# Sheet1.net
KiCad netlist of a schematic drawn in Altium Designer
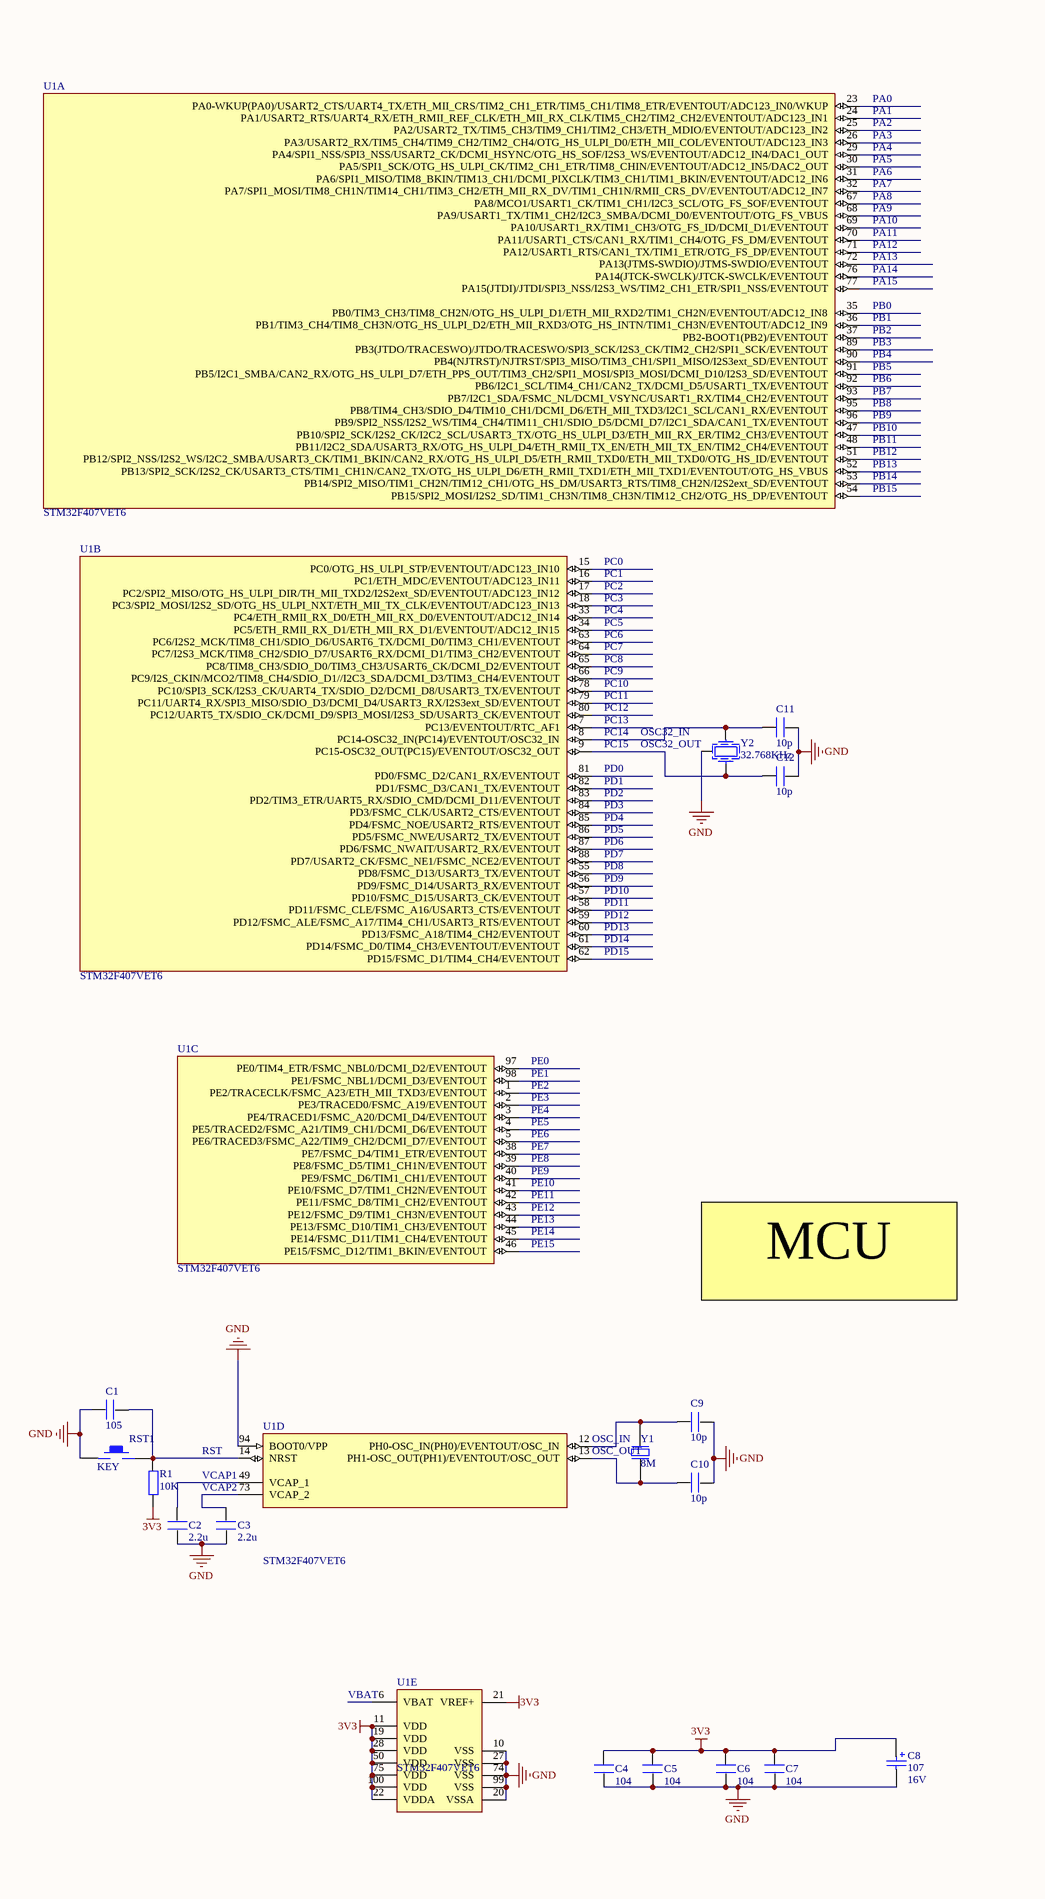
[diagram p0: Sheet1.SchDoc, left]
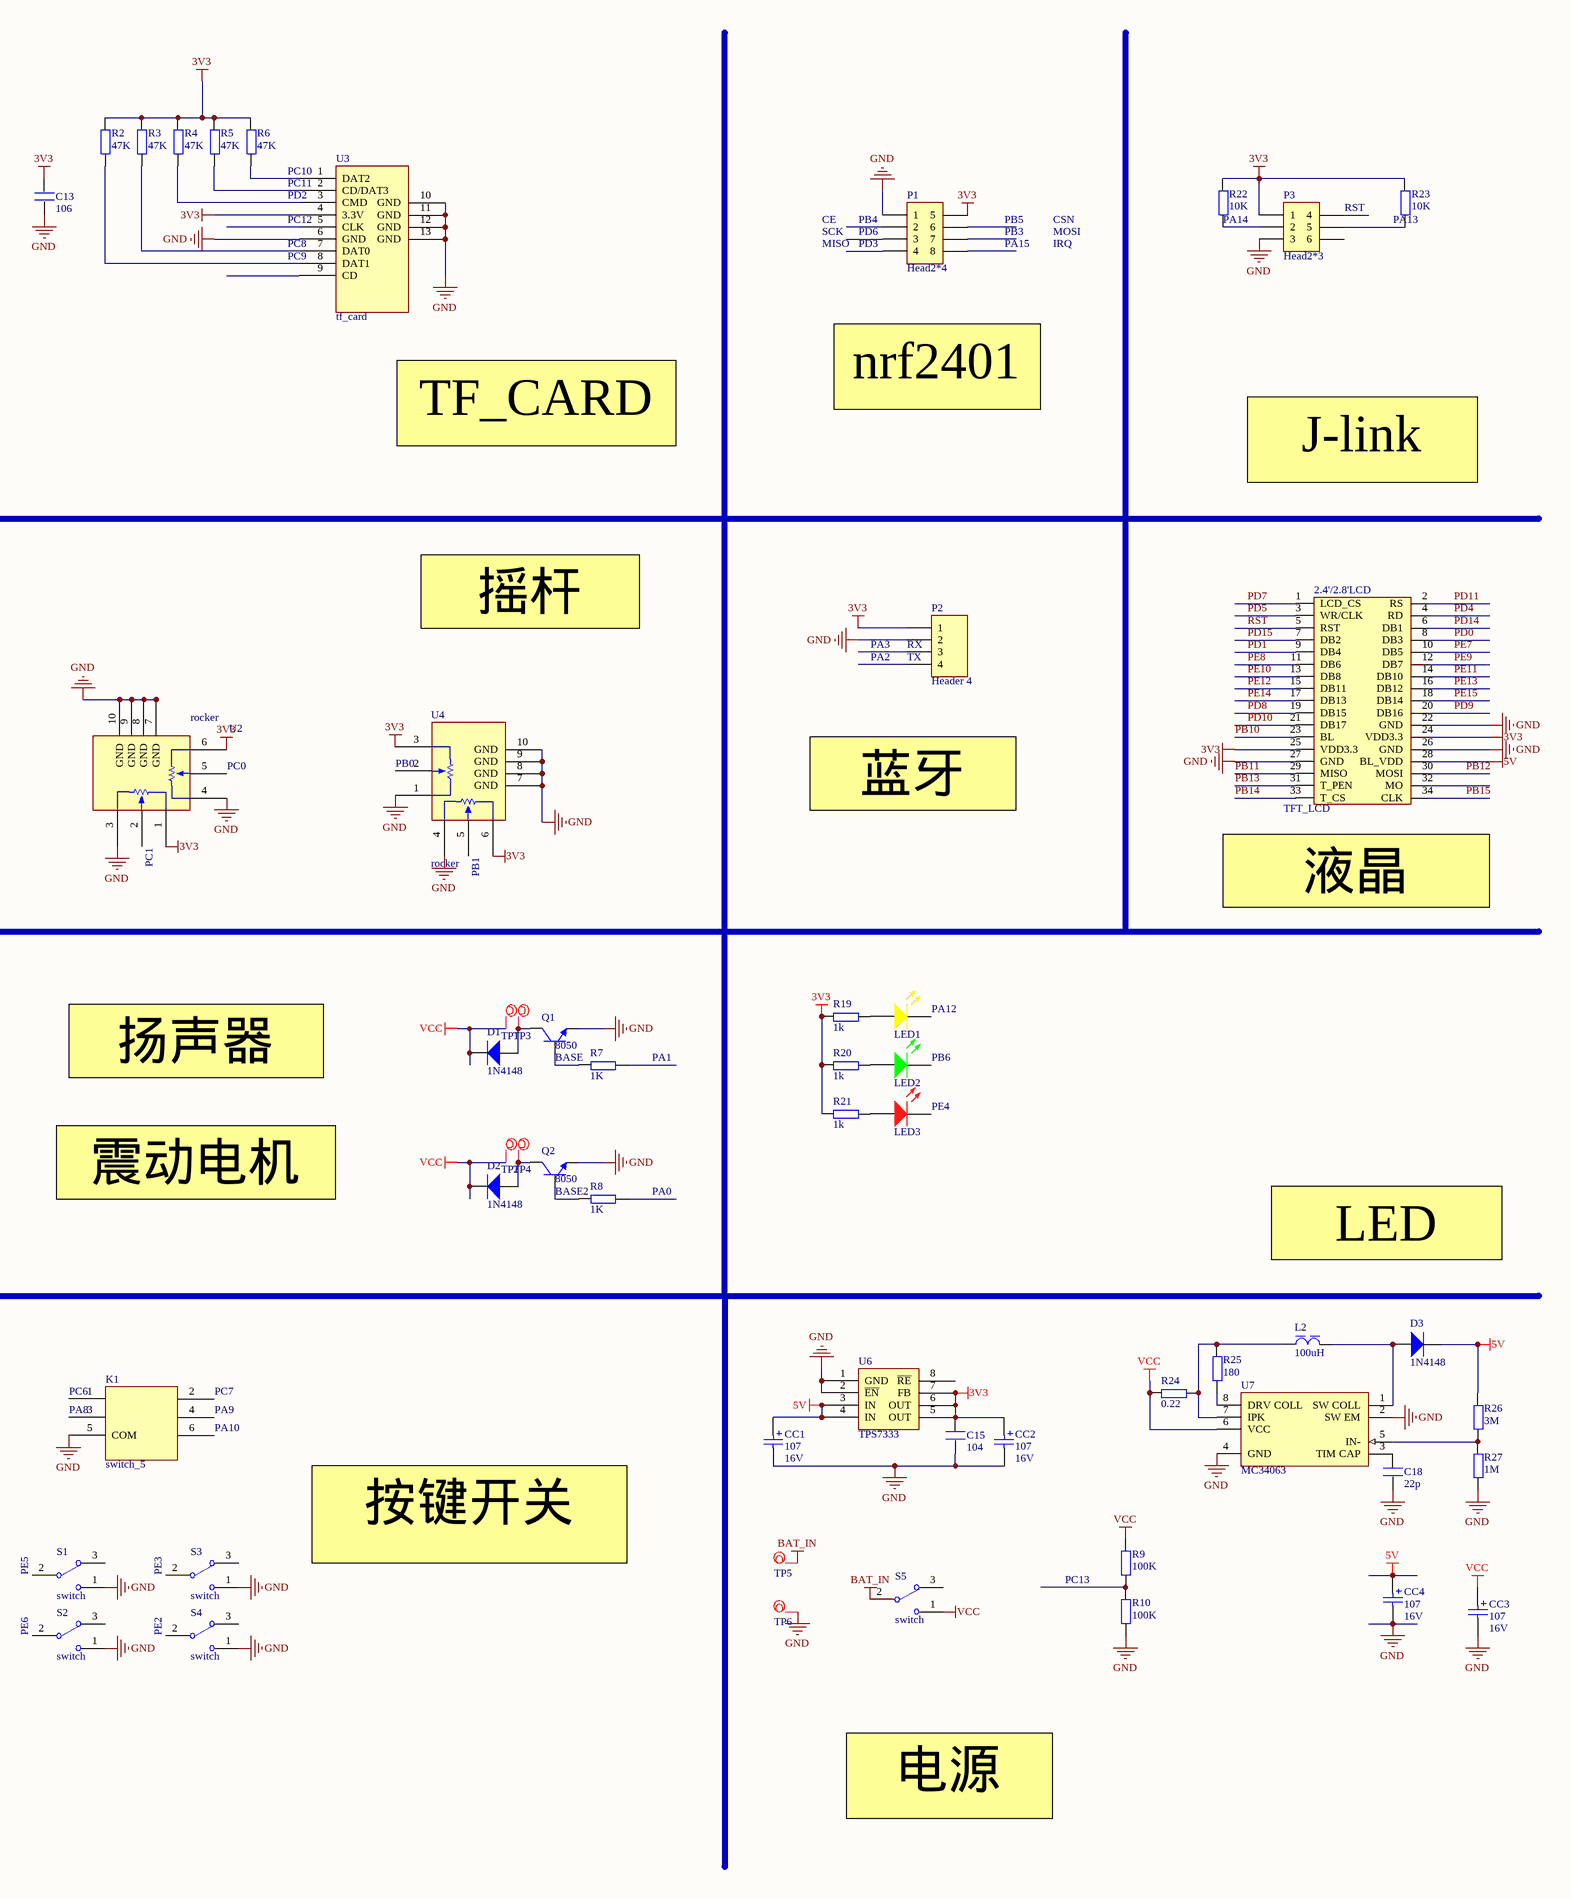
[diagram p1: Sheet1.SchDoc, right]

(export (version "E")
  (design (tool "Eeschema 10.0.6"))
  (components
    (comp (ref "2.4'/2.8'LCD")
      (value "TFT_LCD")
      (footprint "HDR2X17")
      (libsource (lib "战舰STM32开发板底板封装库") (part "TFT_LCD"))
    )
    (comp (ref "C1") (value "105") (footprint "0805C") (libsource (lib "WARSHIP") (part "C")))
    (comp (ref "C2") (value "2.2u") (footprint "0805C") (libsource (lib "WARSHIP") (part "C")))
    (comp (ref "C3") (value "2.2u") (footprint "0805C") (libsource (lib "WARSHIP") (part "C")))
    (comp (ref "C4") (value "104") (footprint "0805C") (libsource (lib "WARSHIP") (part "C")))
    (comp (ref "C5") (value "104") (footprint "0805C") (libsource (lib "WARSHIP") (part "C")))
    (comp (ref "C6") (value "104") (footprint "0805C") (libsource (lib "WARSHIP") (part "C")))
    (comp (ref "C7") (value "104") (footprint "0805C") (libsource (lib "WARSHIP") (part "C")))
    (comp (ref "C8")
      (value "107")
      (footprint "CAPT6032")
      (description "Molded (Tantalum) Capacitor, 2-Leads,")
      (fields (field (name "VOLTAGE") "16V") (field (name "PUBLISHER") "Altium Limited"))
      (libsource (lib "!)Miscellaneous Integrated Library") (part "Cap Tan"))
    )
    (comp (ref "C9") (value "10p") (footprint "0805C") (libsource (lib "WARSHIP") (part "C")))
    (comp (ref "C10") (value "10p") (footprint "0805C") (libsource (lib "WARSHIP") (part "C")))
    (comp (ref "C11") (value "10p") (footprint "0805C") (libsource (lib "WARSHIP") (part "C")))
    (comp (ref "C12") (value "10p") (footprint "0805C") (libsource (lib "WARSHIP") (part "C")))
    (comp (ref "C13") (value "106") (footprint "0805C") (libsource (lib "WARSHIP") (part "C")))
    (comp (ref "C15") (value "104") (footprint "0805C") (libsource (lib "WARSHIP") (part "C")))
    (comp (ref "C18") (value "22p") (footprint "0805C") (libsource (lib "WARSHIP") (part "C")))
    (comp (ref "CC1")
      (value "107")
      (footprint "CAPT6032")
      (description "Molded (Tantalum) Capacitor, 2-Leads,")
      (fields (field (name "VOLTAGE") "16V") (field (name "PUBLISHER") "Altium Limited"))
      (libsource (lib "!)Miscellaneous Integrated Library") (part "Cap Tan"))
    )
    (comp (ref "CC2")
      (value "107")
      (footprint "CAPT6032")
      (description "Molded (Tantalum) Capacitor, 2-Leads,")
      (fields (field (name "VOLTAGE") "16V") (field (name "PUBLISHER") "Altium Limited"))
      (libsource (lib "!)Miscellaneous Integrated Library") (part "Cap Tan"))
    )
    (comp (ref "CC3")
      (value "107")
      (footprint "CAPT6032")
      (description "Molded (Tantalum) Capacitor, 2-Leads,")
      (fields (field (name "VOLTAGE") "16V") (field (name "PUBLISHER") "Altium Limited"))
      (libsource (lib "!)Miscellaneous Integrated Library") (part "Cap Tan"))
    )
    (comp (ref "CC4")
      (value "107")
      (footprint "CAPT6032")
      (description "Molded (Tantalum) Capacitor, 2-Leads,")
      (fields (field (name "VOLTAGE") "16V") (field (name "PUBLISHER") "Altium Limited"))
      (libsource (lib "!)Miscellaneous Integrated Library") (part "Cap Tan"))
    )
    (comp (ref "D1")
      (value "1N4148")
      (footprint "SOD-80[LL-34]")
      (description "SMT Glass Diode, PSpice Model")
      (fields (field (name "PARTNUMBER") "1N4148") (field (name "PUBLISHER") "Altium Limited"))
      (libsource (lib "!)Miscellaneous Integrated Library") (part "Diode 1N4148"))
    )
    (comp (ref "D2")
      (value "1N4148")
      (footprint "SOD-80[LL-34]")
      (description "SMT Glass Diode, PSpice Model")
      (fields (field (name "PARTNUMBER") "1N4148") (field (name "PUBLISHER") "Altium Limited"))
      (libsource (lib "!)Miscellaneous Integrated Library") (part "Diode 1N4148"))
    )
    (comp (ref "D3")
      (value "1N4148")
      (footprint "SOD-80[LL-34]")
      (description "SMT Glass Diode, PSpice Model")
      (fields (field (name "PARTNUMBER") "1N4148") (field (name "PUBLISHER") "Altium Limited"))
      (libsource (lib "!)Miscellaneous Integrated Library") (part "Diode 1N4148"))
    )
    (comp (ref "K1") (value "switch_5") (footprint "switch_5") (libsource (lib "电磁组") (part "switch_5")))
    (comp (ref "L2")
      (value "100uH")
      (footprint "CD75")
      (description "Power Inductor, Ferrite-Core")
      (fields (field (name "PUBLISHER") "Altium Limited"))
      (libsource (lib "!)Miscellaneous Integrated Library") (part "Ind Power"))
    )
    (comp (ref "LED1")
      (value "LED 3Y")
      (footprint "LED-R3-H5-SINGLE-Y")
      (description "Yellow, 3mm, Typical INFRARED GaAs LED")
      (fields (field (name "PUBLISHER") "Altium Limited"))
      (libsource (lib "!)Miscellaneous Integrated Library") (part "LED 3Y"))
    )
    (comp (ref "LED2")
      (value "LED 3G")
      (footprint "LED-R3-H5-SINGLE-G")
      (description "Green, 3mm, Typical INFRARED GaAs LED")
      (fields (field (name "PUBLISHER") "Altium Limited"))
      (libsource (lib "!)Miscellaneous Integrated Library") (part "LED 3G"))
    )
    (comp (ref "LED3")
      (value "LED 3R")
      (footprint "LED-R3-H5-SINGLE-R")
      (description "Red, 3mm, Typical INFRARED GaAs LED")
      (fields (field (name "PUBLISHER") "Altium Limited"))
      (libsource (lib "!)Miscellaneous Integrated Library") (part "LED 3R"))
    )
    (comp (ref "P1")
      (value "Head2*4")
      (footprint "Header2x4_chip")
      (libsource (lib "电磁组") (part "Header2x4"))
    )
    (comp (ref "P2")
      (value "Header 4")
      (footprint "HX2.54V-4")
      (description "Header, 4-Pin")
      (fields (field (name "PUBLISHER") "Altium Limited"))
      (libsource (lib "!)Miscellaneous Integrated Library") (part "Header 4"))
    )
    (comp (ref "P3")
      (value "Head2*3")
      (footprint "Header2x3_chip")
      (libsource (lib "电磁组") (part "Header2x3"))
    )
    (comp (ref "Q1")
      (value "8050")
      (footprint "SOT23")
      (description "NPN Bipolar Transistor")
      (fields (field (name "PARTNUMBER") "8050") (field (name "PUBLISHER") "Altium Limited"))
      (libsource (lib "!)Miscellaneous Integrated Library") (part "NPN BC817-40"))
    )
    (comp (ref "Q2")
      (value "8050")
      (footprint "SOT23")
      (description "NPN Bipolar Transistor")
      (fields (field (name "PARTNUMBER") "8050") (field (name "PUBLISHER") "Altium Limited"))
      (libsource (lib "!)Miscellaneous Integrated Library") (part "NPN BC817-40"))
    )
    (comp (ref "R1") (value "10K") (footprint "0805R") (libsource (lib "WARSHIP") (part "R")))
    (comp (ref "R2") (value "47K") (footprint "0805R") (libsource (lib "WARSHIP") (part "R")))
    (comp (ref "R3") (value "47K") (footprint "0805R") (libsource (lib "WARSHIP") (part "R")))
    (comp (ref "R4") (value "47K") (footprint "0805R") (libsource (lib "WARSHIP") (part "R")))
    (comp (ref "R5") (value "47K") (footprint "0805R") (libsource (lib "WARSHIP") (part "R")))
    (comp (ref "R6") (value "47K") (footprint "0805R") (libsource (lib "WARSHIP") (part "R")))
    (comp (ref "R7") (value "1K") (footprint "0805R") (libsource (lib "WARSHIP") (part "R")))
    (comp (ref "R8") (value "1K") (footprint "0805R") (libsource (lib "WARSHIP") (part "R")))
    (comp (ref "R9") (value "100K") (footprint "0805R") (libsource (lib "WARSHIP") (part "R")))
    (comp (ref "R10") (value "100K") (footprint "0805R") (libsource (lib "WARSHIP") (part "R")))
    (comp (ref "R19") (value "1k") (footprint "0805R") (libsource (lib "WARSHIP") (part "R")))
    (comp (ref "R20") (value "1k") (footprint "0805R") (libsource (lib "WARSHIP") (part "R")))
    (comp (ref "R21") (value "1k") (footprint "0805R") (libsource (lib "WARSHIP") (part "R")))
    (comp (ref "R22") (value "10K") (footprint "0805R") (libsource (lib "WARSHIP") (part "R")))
    (comp (ref "R23") (value "10K") (footprint "0805R") (libsource (lib "WARSHIP") (part "R")))
    (comp (ref "R24") (value "0.22") (footprint "0805R") (libsource (lib "WARSHIP") (part "R")))
    (comp (ref "R25") (value "180") (footprint "0805R") (libsource (lib "WARSHIP") (part "R")))
    (comp (ref "R26") (value "3M") (footprint "0805R") (libsource (lib "WARSHIP") (part "R")))
    (comp (ref "R27") (value "1M") (footprint "0805R") (libsource (lib "WARSHIP") (part "R")))
    (comp (ref "RST1") (value "KEY") (footprint "KEY") (libsource (lib "电磁组") (part "KEY")))
    (comp (ref "S1") (value "switch") (footprint "switch4") (libsource (lib "电磁组") (part "MIANkey")))
    (comp (ref "S2") (value "switch") (footprint "switch4") (libsource (lib "电磁组") (part "MIANkey")))
    (comp (ref "S3") (value "switch") (footprint "switch4") (libsource (lib "电磁组") (part "MIANkey")))
    (comp (ref "S4") (value "switch") (footprint "switch4") (libsource (lib "电磁组") (part "MIANkey")))
    (comp (ref "S5") (value "switch") (footprint "swtich3") (libsource (lib "电磁组") (part "MIANkey")))
    (comp (ref "TP1")
      (value "Test Point")
      (footprint "TESTPOINT_PAD_3")
      (description "Test Point for Manufature")
      (libsource (lib "!)Miscellaneous Integrated Library") (part "Test Point"))
    )
    (comp (ref "TP2")
      (value "Test Point")
      (footprint "TESTPOINT_PAD_3")
      (description "Test Point for Manufature")
      (libsource (lib "!)Miscellaneous Integrated Library") (part "Test Point"))
    )
    (comp (ref "TP3")
      (value "Test Point")
      (footprint "TESTPOINT_PAD_3")
      (description "Test Point for Manufature")
      (libsource (lib "!)Miscellaneous Integrated Library") (part "Test Point"))
    )
    (comp (ref "TP4")
      (value "Test Point")
      (footprint "TESTPOINT_PAD_3")
      (description "Test Point for Manufature")
      (libsource (lib "!)Miscellaneous Integrated Library") (part "Test Point"))
    )
    (comp (ref "TP5")
      (value "Test Point")
      (footprint "TESTPOINT_PAD_3")
      (description "Test Point for Manufature")
      (libsource (lib "!)Miscellaneous Integrated Library") (part "Test Point"))
    )
    (comp (ref "TP6")
      (value "Test Point")
      (footprint "TESTPOINT_PAD_3")
      (description "Test Point for Manufature")
      (libsource (lib "!)Miscellaneous Integrated Library") (part "Test Point"))
    )
    (comp (ref "U1")
      (value "STM32F407VET6")
      (footprint "LQFP100_M")
      (libsource (lib "STMicroelectronics STM32 F4") (part "STM32F407VET6"))
    )
    (comp (ref "U2") (value "rocker") (footprint "Rocker") (libsource (lib "电磁组") (part "rocker")))
    (comp (ref "U3") (value "tf_card") (footprint "TF-2") (libsource (lib "电磁组") (part "TF- SDIO")))
    (comp (ref "U4") (value "rocker") (footprint "Rocker") (libsource (lib "") (part "rocker_1")))
    (comp (ref "U6") (value "TPS7333") (footprint "TPS7333") (libsource (lib "Schlib1") (part "TPS7333")))
    (comp (ref "U7")
      (value "MC34063")
      (footprint "SOIC8")
      (description "DC-to-DC Converter Control Circuit")
      (fields (field (name "PARTNUMBER") "MC34063"))
      (libsource (lib "!)Miscellaneous Integrated Library") (part "MC34063"))
    )
    (comp (ref "Y1")
      (value "8M")
      (footprint "XTAL-SMD")
      (description "Crystal Oscillator")
      (fields (field (name "PUBLISHER") "Altium Limited"))
      (libsource (lib "!)Miscellaneous Integrated Library") (part "XTAL"))
    )
    (comp (ref "Y2")
      (value "32.768KHz")
      (footprint "XTAL")
      (description "3-pin Crystal Oscillator, Case Shelter")
      (libsource (lib "!)Miscellaneous Integrated Library") (part "XTAL 3P"))
    )
  )
  (nets
    (net (code "1") (name "/BASE") (class "Default")
      (node (ref "Q1") (pin "1") (pinfunction "B_1") (pintype "passive"))
      (node (ref "R7") (pin "1") (pintype "passive"))
    )
    (net (code "2") (name "/BASE2") (class "Default")
      (node (ref "Q2") (pin "1") (pinfunction "B_1") (pintype "passive"))
      (node (ref "R8") (pin "1") (pintype "passive"))
    )
    (net (code "8") (name "/OSC32_IN") (class "Default")
      (node (ref "C11") (pin "1") (pintype "passive"))
      (node (ref "U1") (pin "8") (pinfunction "PC14-OSC32_IN(PC14)/EVENTOUT/OSC32_IN_8") (pintype "bidirectional"))
      (node (ref "Y2") (pin "1") (pintype "passive"))
    )
    (net (code "9") (name "/OSC32_OUT") (class "Default")
      (node (ref "C12") (pin "1") (pintype "passive"))
      (node (ref "U1") (pin "9") (pinfunction "PC15-OSC32_OUT(PC15)/EVENTOUT/OSC32_OUT_9") (pintype "bidirectional"))
      (node (ref "Y2") (pin "2") (pintype "passive"))
    )
    (net (code "10") (name "/OSC_IN") (class "Default")
      (node (ref "C9") (pin "1") (pintype "passive"))
      (node (ref "U1") (pin "12") (pinfunction "PH0-OSC_IN(PH0)/EVENTOUT/OSC_IN_12") (pintype "bidirectional"))
      (node (ref "Y1") (pin "2") (pinfunction "OSC2_2") (pintype "passive"))
    )
    (net (code "11") (name "/OSC_OUT") (class "Default")
      (node (ref "C10") (pin "1") (pintype "passive"))
      (node (ref "U1") (pin "13") (pinfunction "PH1-OSC_OUT(PH1)/EVENTOUT/OSC_OUT_13") (pintype "bidirectional"))
      (node (ref "Y1") (pin "1") (pinfunction "OSC1_1") (pintype "passive"))
    )
    (net (code "12") (name "/PA0") (class "Default")
      (node (ref "R8") (pin "2") (pintype "passive"))
      (node (ref "U1") (pin "23") (pinfunction "PA0-WKUP(PA0)/USART2_CTS/UART4_TX/ETH_MII_CRS/TIM2_CH1_ETR/TIM5_CH1/TIM8_ETR/EVENTOUT/ADC123_IN0/WKUP_23") (pintype "bidirectional"))
    )
    (net (code "13") (name "/PA1") (class "Default")
      (node (ref "R7") (pin "2") (pintype "passive"))
      (node (ref "U1") (pin "24") (pinfunction "PA1/USART2_RTS/UART4_RX/ETH_RMII_REF_CLK/ETH_MII_RX_CLK/TIM5_CH2/TIM2_CH2/EVENTOUT/ADC123_IN1_24") (pintype "bidirectional"))
    )
    (net (code "14") (name "/PA2") (class "Default")
      (node (ref "P2") (pin "4") (pinfunction "4_4") (pintype "passive"))
      (node (ref "U1") (pin "25") (pinfunction "PA2/USART2_TX/TIM5_CH3/TIM9_CH1/TIM2_CH3/ETH_MDIO/EVENTOUT/ADC123_IN2_25") (pintype "bidirectional"))
    )
    (net (code "15") (name "/PA3") (class "Default")
      (node (ref "P2") (pin "3") (pinfunction "3_3") (pintype "passive"))
      (node (ref "U1") (pin "26") (pinfunction "PA3/USART2_RX/TIM5_CH4/TIM9_CH2/TIM2_CH4/OTG_HS_ULPI_D0/ETH_MII_COL/EVENTOUT/ADC123_IN3_26") (pintype "bidirectional"))
    )
    (net (code "16") (name "/PA4") (class "Default")
      (node (ref "U1") (pin "29") (pinfunction "PA4/SPI1_NSS/SPI3_NSS/USART2_CK/DCMI_HSYNC/OTG_HS_SOF/I2S3_WS/EVENTOUT/ADC12_IN4/DAC1_OUT_29") (pintype "bidirectional"))
    )
    (net (code "17") (name "/PA5") (class "Default")
      (node (ref "U1") (pin "30") (pinfunction "PA5/SPI1_SCK/OTG_HS_ULPI_CK/TIM2_CH1_ETR/TIM8_CHIN/EVENTOUT/ADC12_IN5/DAC2_OUT_30") (pintype "bidirectional"))
    )
    (net (code "18") (name "/PA6") (class "Default")
      (node (ref "U1") (pin "31") (pinfunction "PA6/SPI1_MISO/TIM8_BKIN/TIM13_CH1/DCMI_PIXCLK/TIM3_CH1/TIM1_BKIN/EVENTOUT/ADC12_IN6_31") (pintype "bidirectional"))
    )
    (net (code "19") (name "/PA7") (class "Default")
      (node (ref "U1") (pin "32") (pinfunction "PA7/SPI1_MOSI/TIM8_CH1N/TIM14_CH1/TIM3_CH2/ETH_MII_RX_DV/TIM1_CH1N/RMII_CRS_DV/EVENTOUT/ADC12_IN7_32") (pintype "bidirectional"))
    )
    (net (code "20") (name "/PA8") (class "Default")
      (node (ref "K1") (pin "3") (pintype "passive"))
      (node (ref "U1") (pin "67") (pinfunction "PA8/MCO1/USART1_CK/TIM1_CH1/I2C3_SCL/OTG_FS_SOF/EVENTOUT_67") (pintype "bidirectional"))
    )
    (net (code "21") (name "/PA9") (class "Default")
      (node (ref "K1") (pin "4") (pintype "passive"))
      (node (ref "U1") (pin "68") (pinfunction "PA9/USART1_TX/TIM1_CH2/I2C3_SMBA/DCMI_D0/EVENTOUT/OTG_FS_VBUS_68") (pintype "bidirectional"))
    )
    (net (code "22") (name "/PA10") (class "Default")
      (node (ref "K1") (pin "6") (pintype "passive"))
      (node (ref "U1") (pin "69") (pinfunction "PA10/USART1_RX/TIM1_CH3/OTG_FS_ID/DCMI_D1/EVENTOUT_69") (pintype "bidirectional"))
    )
    (net (code "23") (name "/PA11") (class "Default")
      (node (ref "U1") (pin "70") (pinfunction "PA11/USART1_CTS/CAN1_RX/TIM1_CH4/OTG_FS_DM/EVENTOUT_70") (pintype "bidirectional"))
    )
    (net (code "24") (name "/PA12") (class "Default")
      (node (ref "LED1") (pin "2") (pinfunction "K_2") (pintype "passive"))
      (node (ref "U1") (pin "71") (pinfunction "PA12/USART1_RTS/CAN1_TX/TIM1_ETR/OTG_FS_DP/EVENTOUT_71") (pintype "bidirectional"))
    )
    (net (code "25") (name "/PA13") (class "Default")
      (node (ref "P3") (pin "5") (pinfunction "5_5") (pintype "passive"))
      (node (ref "R23") (pin "1") (pintype "passive"))
      (node (ref "U1") (pin "72") (pinfunction "PA13(JTMS-SWDIO)/JTMS-SWDIO/EVENTOUT_72") (pintype "bidirectional"))
    )
    (net (code "26") (name "/PA14") (class "Default")
      (node (ref "P3") (pin "2") (pinfunction "2_2") (pintype "passive"))
      (node (ref "R22") (pin "1") (pintype "passive"))
      (node (ref "U1") (pin "76") (pinfunction "PA14(JTCK-SWCLK)/JTCK-SWCLK/EVENTOUT_76") (pintype "bidirectional"))
    )
    (net (code "27") (name "/PA15") (class "Default")
      (node (ref "P1") (pin "8") (pinfunction "8_8") (pintype "passive"))
      (node (ref "U1") (pin "77") (pinfunction "PA15(JTDI)/JTDI/SPI3_NSS/I2S3_WS/TIM2_CH1_ETR/SPI1_NSS/EVENTOUT_77") (pintype "bidirectional"))
    )
    (net (code "28") (name "/PB0") (class "Default")
      (node (ref "U1") (pin "35") (pinfunction "PB0/TIM3_CH3/TIM8_CH2N/OTG_HS_ULPI_D1/ETH_MII_RXD2/TIM1_CH2N/EVENTOUT/ADC12_IN8_35") (pintype "bidirectional"))
      (node (ref "U4") (pin "2") (pintype "passive"))
    )
    (net (code "29") (name "/PB1") (class "Default")
      (node (ref "U1") (pin "36") (pinfunction "PB1/TIM3_CH4/TIM8_CH3N/OTG_HS_ULPI_D2/ETH_MII_RXD3/OTG_HS_INTN/TIM1_CH3N/EVENTOUT/ADC12_IN9_36") (pintype "bidirectional"))
      (node (ref "U4") (pin "5") (pintype "passive"))
    )
    (net (code "30") (name "/PB2") (class "Default")
      (node (ref "U1") (pin "37") (pinfunction "PB2-BOOT1(PB2)/EVENTOUT_37") (pintype "bidirectional"))
    )
    (net (code "31") (name "/PB3") (class "Default")
      (node (ref "P1") (pin "7") (pinfunction "7_7") (pintype "passive"))
      (node (ref "U1") (pin "89") (pinfunction "PB3(JTDO/TRACESWO)/JTDO/TRACESWO/SPI3_SCK/I2S3_CK/TIM2_CH2/SPI1_SCK/EVENTOUT_89") (pintype "bidirectional"))
    )
    (net (code "32") (name "/PB4") (class "Default")
      (node (ref "P1") (pin "2") (pinfunction "2_2") (pintype "passive"))
      (node (ref "U1") (pin "90") (pinfunction "PB4(NJTRST)/NJTRST/SPI3_MISO/TIM3_CH1/SPI1_MISO/I2S3ext_SD/EVENTOUT_90") (pintype "bidirectional"))
    )
    (net (code "33") (name "/PB5") (class "Default")
      (node (ref "P1") (pin "6") (pinfunction "6_6") (pintype "passive"))
      (node (ref "U1") (pin "91") (pinfunction "PB5/I2C1_SMBA/CAN2_RX/OTG_HS_ULPI_D7/ETH_PPS_OUT/TIM3_CH2/SPI1_MOSI/SPI3_MOSI/DCMI_D10/I2S3_SD/EVENTOUT_91") (pintype "bidirectional"))
    )
    (net (code "34") (name "/PB6") (class "Default")
      (node (ref "LED2") (pin "2") (pinfunction "K_2") (pintype "passive"))
      (node (ref "U1") (pin "92") (pinfunction "PB6/I2C1_SCL/TIM4_CH1/CAN2_TX/DCMI_D5/USART1_TX/EVENTOUT_92") (pintype "bidirectional"))
    )
    (net (code "35") (name "/PB7") (class "Default")
      (node (ref "U1") (pin "93") (pinfunction "PB7/I2C1_SDA/FSMC_NL/DCMI_VSYNC/USART1_RX/TIM4_CH2/EVENTOUT_93") (pintype "bidirectional"))
    )
    (net (code "36") (name "/PB8") (class "Default")
      (node (ref "U1") (pin "95") (pinfunction "PB8/TIM4_CH3/SDIO_D4/TIM10_CH1/DCMI_D6/ETH_MII_TXD3/I2C1_SCL/CAN1_RX/EVENTOUT_95") (pintype "bidirectional"))
    )
    (net (code "37") (name "/PB9") (class "Default")
      (node (ref "U1") (pin "96") (pinfunction "PB9/SPI2_NSS/I2S2_WS/TIM4_CH4/TIM11_CH1/SDIO_D5/DCMI_D7/I2C1_SDA/CAN1_TX/EVENTOUT_96") (pintype "bidirectional"))
    )
    (net (code "38") (name "/PB10") (class "Default")
      (node (ref "2.4'/2.8'LCD") (pin "23") (pinfunction "BL_23") (pintype "passive"))
      (node (ref "U1") (pin "47") (pinfunction "PB10/SPI2_SCK/I2S2_CK/I2C2_SCL/USART3_TX/OTG_HS_ULPI_D3/ETH_MII_RX_ER/TIM2_CH3/EVENTOUT_47") (pintype "bidirectional"))
    )
    (net (code "39") (name "/PB11") (class "Default")
      (node (ref "2.4'/2.8'LCD") (pin "29") (pinfunction "MISO_29") (pintype "passive"))
      (node (ref "U1") (pin "48") (pinfunction "PB11/I2C2_SDA/USART3_RX/OTG_HS_ULPI_D4/ETH_RMII_TX_EN/ETH_MII_TX_EN/TIM2_CH4/EVENTOUT_48") (pintype "bidirectional"))
    )
    (net (code "40") (name "/PB12") (class "Default")
      (node (ref "2.4'/2.8'LCD") (pin "30") (pinfunction "MOSI_30") (pintype "passive"))
      (node (ref "U1") (pin "51") (pinfunction "PB12/SPI2_NSS/I2S2_WS/I2C2_SMBA/USART3_CK/TIM1_BKIN/CAN2_RX/OTG_HS_ULPI_D5/ETH_RMII_TXD0/ETH_MII_TXD0/OTG_HS_ID/EVENTOUT_51") (pintype "bidirectional"))
    )
    (net (code "41") (name "/PB13") (class "Default")
      (node (ref "2.4'/2.8'LCD") (pin "31") (pinfunction "T_PEN_31") (pintype "passive"))
      (node (ref "U1") (pin "52") (pinfunction "PB13/SPI2_SCK/I2S2_CK/USART3_CTS/TIM1_CH1N/CAN2_TX/OTG_HS_ULPI_D6/ETH_RMII_TXD1/ETH_MII_TXD1/EVENTOUT/OTG_HS_VBUS_52") (pintype "bidirectional"))
    )
    (net (code "42") (name "/PB14") (class "Default")
      (node (ref "2.4'/2.8'LCD") (pin "33") (pinfunction "T_CS_33") (pintype "passive"))
      (node (ref "U1") (pin "53") (pinfunction "PB14/SPI2_MISO/TIM1_CH2N/TIM12_CH1/OTG_HS_DM/USART3_RTS/TIM8_CH2N/I2S2ext_SD/EVENTOUT_53") (pintype "bidirectional"))
    )
    (net (code "43") (name "/PB15") (class "Default")
      (node (ref "2.4'/2.8'LCD") (pin "34") (pinfunction "CLK_34") (pintype "passive"))
      (node (ref "U1") (pin "54") (pinfunction "PB15/SPI2_MOSI/I2S2_SD/TIM1_CH3N/TIM8_CH3N/TIM12_CH2/OTG_HS_DP/EVENTOUT_54") (pintype "bidirectional"))
    )
    (net (code "44") (name "/PC0") (class "Default")
      (node (ref "U1") (pin "15") (pinfunction "PC0/OTG_HS_ULPI_STP/EVENTOUT/ADC123_IN10_15") (pintype "bidirectional"))
      (node (ref "U2") (pin "5") (pintype "passive"))
    )
    (net (code "45") (name "/PC1") (class "Default")
      (node (ref "U1") (pin "16") (pinfunction "PC1/ETH_MDC/EVENTOUT/ADC123_IN11_16") (pintype "bidirectional"))
      (node (ref "U2") (pin "2") (pintype "passive"))
    )
    (net (code "46") (name "/PC2") (class "Default")
      (node (ref "U1") (pin "17") (pinfunction "PC2/SPI2_MISO/OTG_HS_ULPI_DIR/TH_MII_TXD2/I2S2ext_SD/EVENTOUT/ADC123_IN12_17") (pintype "bidirectional"))
    )
    (net (code "47") (name "/PC3") (class "Default")
      (node (ref "U1") (pin "18") (pinfunction "PC3/SPI2_MOSI/I2S2_SD/OTG_HS_ULPI_NXT/ETH_MII_TX_CLK/EVENTOUT/ADC123_IN13_18") (pintype "bidirectional"))
    )
    (net (code "48") (name "/PC4") (class "Default")
      (node (ref "U1") (pin "33") (pinfunction "PC4/ETH_RMII_RX_D0/ETH_MII_RX_D0/EVENTOUT/ADC12_IN14_33") (pintype "bidirectional"))
    )
    (net (code "49") (name "/PC5") (class "Default")
      (node (ref "U1") (pin "34") (pinfunction "PC5/ETH_RMII_RX_D1/ETH_MII_RX_D1/EVENTOUT/ADC12_IN15_34") (pintype "bidirectional"))
    )
    (net (code "50") (name "/PC6") (class "Default")
      (node (ref "K1") (pin "1") (pintype "passive"))
      (node (ref "U1") (pin "63") (pinfunction "PC6/I2S2_MCK/TIM8_CH1/SDIO_D6/USART6_TX/DCMI_D0/TIM3_CH1/EVENTOUT_63") (pintype "bidirectional"))
    )
    (net (code "51") (name "/PC7") (class "Default")
      (node (ref "K1") (pin "2") (pintype "passive"))
      (node (ref "U1") (pin "64") (pinfunction "PC7/I2S3_MCK/TIM8_CH2/SDIO_D7/USART6_RX/DCMI_D1/TIM3_CH2/EVENTOUT_64") (pintype "bidirectional"))
    )
    (net (code "52") (name "/PC8") (class "Default")
      (node (ref "R3") (pin "1") (pintype "passive"))
      (node (ref "U1") (pin "65") (pinfunction "PC8/TIM8_CH3/SDIO_D0/TIM3_CH3/USART6_CK/DCMI_D2/EVENTOUT_65") (pintype "bidirectional"))
      (node (ref "U3") (pin "7") (pinfunction "DAT0_7") (pintype "passive"))
    )
    (net (code "53") (name "/PC9") (class "Default")
      (node (ref "R2") (pin "1") (pintype "passive"))
      (node (ref "U1") (pin "66") (pinfunction "PC9/I2S_CKIN/MCO2/TIM8_CH4/SDIO_D1//I2C3_SDA/DCMI_D3/TIM3_CH4/EVENTOUT_66") (pintype "bidirectional"))
      (node (ref "U3") (pin "8") (pinfunction "DAT1_8") (pintype "passive"))
    )
    (net (code "54") (name "/PC10") (class "Default")
      (node (ref "R6") (pin "1") (pintype "passive"))
      (node (ref "U1") (pin "78") (pinfunction "PC10/SPI3_SCK/I2S3_CK/UART4_TX/SDIO_D2/DCMI_D8/USART3_TX/EVENTOUT_78") (pintype "bidirectional"))
      (node (ref "U3") (pin "1") (pinfunction "DAT2_1") (pintype "passive"))
    )
    (net (code "55") (name "/PC11") (class "Default")
      (node (ref "R5") (pin "1") (pintype "passive"))
      (node (ref "U1") (pin "79") (pinfunction "PC11/UART4_RX/SPI3_MISO/SDIO_D3/DCMI_D4/USART3_RX/I2S3ext_SD/EVENTOUT_79") (pintype "bidirectional"))
      (node (ref "U3") (pin "2") (pinfunction "CD/DAT3_2") (pintype "passive"))
    )
    (net (code "56") (name "/PC12") (class "Default")
      (node (ref "U1") (pin "80") (pinfunction "PC12/UART5_TX/SDIO_CK/DCMI_D9/SPI3_MOSI/I2S3_SD/USART3_CK/EVENTOUT_80") (pintype "bidirectional"))
      (node (ref "U3") (pin "5") (pinfunction "CLK_5") (pintype "passive"))
    )
    (net (code "57") (name "/PC13") (class "Default")
      (node (ref "R10") (pin "2") (pintype "passive"))
      (node (ref "R9") (pin "1") (pintype "passive"))
      (node (ref "U1") (pin "7") (pinfunction "PC13/EVENTOUT/RTC_AF1_7") (pintype "bidirectional"))
    )
    (net (code "58") (name "/PD0") (class "Default")
      (node (ref "2.4'/2.8'LCD") (pin "8") (pinfunction "DB3_8") (pintype "passive"))
      (node (ref "U1") (pin "81") (pinfunction "PD0/FSMC_D2/CAN1_RX/EVENTOUT_81") (pintype "bidirectional"))
    )
    (net (code "59") (name "/PD1") (class "Default")
      (node (ref "2.4'/2.8'LCD") (pin "9") (pinfunction "DB4_9") (pintype "passive"))
      (node (ref "U1") (pin "82") (pinfunction "PD1/FSMC_D3/CAN1_TX/EVENTOUT_82") (pintype "bidirectional"))
    )
    (net (code "60") (name "/PD2") (class "Default")
      (node (ref "R4") (pin "1") (pintype "passive"))
      (node (ref "U1") (pin "83") (pinfunction "PD2/TIM3_ETR/UART5_RX/SDIO_CMD/DCMI_D11/EVENTOUT_83") (pintype "bidirectional"))
      (node (ref "U3") (pin "3") (pinfunction "CMD_3") (pintype "passive"))
    )
    (net (code "61") (name "/PD3") (class "Default")
      (node (ref "P1") (pin "4") (pinfunction "4_4") (pintype "passive"))
      (node (ref "U1") (pin "84") (pinfunction "PD3/FSMC_CLK/USART2_CTS/EVENTOUT_84") (pintype "bidirectional"))
    )
    (net (code "62") (name "/PD4") (class "Default")
      (node (ref "2.4'/2.8'LCD") (pin "4") (pinfunction "RD_4") (pintype "passive"))
      (node (ref "U1") (pin "85") (pinfunction "PD4/FSMC_NOE/USART2_RTS/EVENTOUT_85") (pintype "bidirectional"))
    )
    (net (code "63") (name "/PD5") (class "Default")
      (node (ref "2.4'/2.8'LCD") (pin "3") (pinfunction "WR/CLK_3") (pintype "passive"))
      (node (ref "U1") (pin "86") (pinfunction "PD5/FSMC_NWE/USART2_TX/EVENTOUT_86") (pintype "bidirectional"))
    )
    (net (code "64") (name "/PD6") (class "Default")
      (node (ref "P1") (pin "3") (pinfunction "3_3") (pintype "passive"))
      (node (ref "U1") (pin "87") (pinfunction "PD6/FSMC_NWAIT/USART2_RX/EVENTOUT_87") (pintype "bidirectional"))
    )
    (net (code "65") (name "/PD7") (class "Default")
      (node (ref "2.4'/2.8'LCD") (pin "1") (pinfunction "LCD_CS_1") (pintype "passive"))
      (node (ref "U1") (pin "88") (pinfunction "PD7/USART2_CK/FSMC_NE1/FSMC_NCE2/EVENTOUT_88") (pintype "bidirectional"))
    )
    (net (code "66") (name "/PD8") (class "Default")
      (node (ref "2.4'/2.8'LCD") (pin "19") (pinfunction "DB15_19") (pintype "passive"))
      (node (ref "U1") (pin "55") (pinfunction "PD8/FSMC_D13/USART3_TX/EVENTOUT_55") (pintype "bidirectional"))
    )
    (net (code "67") (name "/PD9") (class "Default")
      (node (ref "2.4'/2.8'LCD") (pin "20") (pinfunction "DB16_20") (pintype "passive"))
      (node (ref "U1") (pin "56") (pinfunction "PD9/FSMC_D14/USART3_RX/EVENTOUT_56") (pintype "bidirectional"))
    )
    (net (code "68") (name "/PD10") (class "Default")
      (node (ref "2.4'/2.8'LCD") (pin "21") (pinfunction "DB17_21") (pintype "passive"))
      (node (ref "U1") (pin "57") (pinfunction "PD10/FSMC_D15/USART3_CK/EVENTOUT_57") (pintype "bidirectional"))
    )
    (net (code "69") (name "/PD11") (class "Default")
      (node (ref "2.4'/2.8'LCD") (pin "2") (pinfunction "RS_2") (pintype "passive"))
      (node (ref "U1") (pin "58") (pinfunction "PD11/FSMC_CLE/FSMC_A16/USART3_CTS/EVENTOUT_58") (pintype "bidirectional"))
    )
    (net (code "70") (name "/PD12") (class "Default")
      (node (ref "U1") (pin "59") (pinfunction "PD12/FSMC_ALE/FSMC_A17/TIM4_CH1/USART3_RTS/EVENTOUT_59") (pintype "bidirectional"))
    )
    (net (code "71") (name "/PD13") (class "Default")
      (node (ref "U1") (pin "60") (pinfunction "PD13/FSMC_A18/TIM4_CH2/EVENTOUT_60") (pintype "bidirectional"))
    )
    (net (code "72") (name "/PD14") (class "Default")
      (node (ref "2.4'/2.8'LCD") (pin "6") (pinfunction "DB1_6") (pintype "passive"))
      (node (ref "U1") (pin "61") (pinfunction "PD14/FSMC_D0/TIM4_CH3/EVENTOUT/EVENTOUT_61") (pintype "bidirectional"))
    )
    (net (code "73") (name "/PD15") (class "Default")
      (node (ref "2.4'/2.8'LCD") (pin "7") (pinfunction "DB2_7") (pintype "passive"))
      (node (ref "U1") (pin "62") (pinfunction "PD15/FSMC_D1/TIM4_CH4/EVENTOUT_62") (pintype "bidirectional"))
    )
    (net (code "74") (name "/PE0") (class "Default")
      (node (ref "U1") (pin "97") (pinfunction "PE0/TIM4_ETR/FSMC_NBL0/DCMI_D2/EVENTOUT_97") (pintype "bidirectional"))
    )
    (net (code "75") (name "/PE1") (class "Default")
      (node (ref "U1") (pin "98") (pinfunction "PE1/FSMC_NBL1/DCMI_D3/EVENTOUT_98") (pintype "bidirectional"))
    )
    (net (code "76") (name "/PE2") (class "Default")
      (node (ref "S4") (pin "2") (pinfunction "2_2") (pintype "passive"))
      (node (ref "U1") (pin "1") (pinfunction "PE2/TRACECLK/FSMC_A23/ETH_MII_TXD3/EVENTOUT_1") (pintype "bidirectional"))
    )
    (net (code "77") (name "/PE3") (class "Default")
      (node (ref "S3") (pin "2") (pinfunction "2_2") (pintype "passive"))
      (node (ref "U1") (pin "2") (pinfunction "PE3/TRACED0/FSMC_A19/EVENTOUT_2") (pintype "bidirectional"))
    )
    (net (code "78") (name "/PE4") (class "Default")
      (node (ref "LED3") (pin "2") (pinfunction "K_2") (pintype "passive"))
      (node (ref "U1") (pin "3") (pinfunction "PE4/TRACED1/FSMC_A20/DCMI_D4/EVENTOUT_3") (pintype "bidirectional"))
    )
    (net (code "79") (name "/PE5") (class "Default")
      (node (ref "S1") (pin "2") (pinfunction "2_2") (pintype "passive"))
      (node (ref "U1") (pin "4") (pinfunction "PE5/TRACED2/FSMC_A21/TIM9_CH1/DCMI_D6/EVENTOUT_4") (pintype "bidirectional"))
    )
    (net (code "80") (name "/PE6") (class "Default")
      (node (ref "S2") (pin "2") (pinfunction "2_2") (pintype "passive"))
      (node (ref "U1") (pin "5") (pinfunction "PE6/TRACED3/FSMC_A22/TIM9_CH2/DCMI_D7/EVENTOUT_5") (pintype "bidirectional"))
    )
    (net (code "81") (name "/PE7") (class "Default")
      (node (ref "2.4'/2.8'LCD") (pin "10") (pinfunction "DB5_10") (pintype "passive"))
      (node (ref "U1") (pin "38") (pinfunction "PE7/FSMC_D4/TIM1_ETR/EVENTOUT_38") (pintype "bidirectional"))
    )
    (net (code "82") (name "/PE8") (class "Default")
      (node (ref "2.4'/2.8'LCD") (pin "11") (pinfunction "DB6_11") (pintype "passive"))
      (node (ref "U1") (pin "39") (pinfunction "PE8/FSMC_D5/TIM1_CH1N/EVENTOUT_39") (pintype "bidirectional"))
    )
    (net (code "83") (name "/PE9") (class "Default")
      (node (ref "2.4'/2.8'LCD") (pin "12") (pinfunction "DB7_12") (pintype "passive"))
      (node (ref "U1") (pin "40") (pinfunction "PE9/FSMC_D6/TIM1_CH1/EVENTOUT_40") (pintype "bidirectional"))
    )
    (net (code "84") (name "/PE10") (class "Default")
      (node (ref "2.4'/2.8'LCD") (pin "13") (pinfunction "DB8_13") (pintype "passive"))
      (node (ref "U1") (pin "41") (pinfunction "PE10/FSMC_D7/TIM1_CH2N/EVENTOUT_41") (pintype "bidirectional"))
    )
    (net (code "85") (name "/PE11") (class "Default")
      (node (ref "2.4'/2.8'LCD") (pin "14") (pinfunction "DB10_14") (pintype "passive"))
      (node (ref "U1") (pin "42") (pinfunction "PE11/FSMC_D8/TIM1_CH2/EVENTOUT_42") (pintype "bidirectional"))
    )
    (net (code "86") (name "/PE12") (class "Default")
      (node (ref "2.4'/2.8'LCD") (pin "15") (pinfunction "DB11_15") (pintype "passive"))
      (node (ref "U1") (pin "43") (pinfunction "PE12/FSMC_D9/TIM1_CH3N/EVENTOUT_43") (pintype "bidirectional"))
    )
    (net (code "87") (name "/PE13") (class "Default")
      (node (ref "2.4'/2.8'LCD") (pin "16") (pinfunction "DB12_16") (pintype "passive"))
      (node (ref "U1") (pin "44") (pinfunction "PE13/FSMC_D10/TIM1_CH3/EVENTOUT_44") (pintype "bidirectional"))
    )
    (net (code "88") (name "/PE14") (class "Default")
      (node (ref "2.4'/2.8'LCD") (pin "17") (pinfunction "DB13_17") (pintype "passive"))
      (node (ref "U1") (pin "45") (pinfunction "PE14/FSMC_D11/TIM1_CH4/EVENTOUT_45") (pintype "bidirectional"))
    )
    (net (code "89") (name "/PE15") (class "Default")
      (node (ref "2.4'/2.8'LCD") (pin "18") (pinfunction "DB14_18") (pintype "passive"))
      (node (ref "U1") (pin "46") (pinfunction "PE15/FSMC_D12/TIM1_BKIN/EVENTOUT_46") (pintype "bidirectional"))
    )
    (net (code "90") (name "/RST") (class "Default")
      (node (ref "2.4'/2.8'LCD") (pin "5") (pinfunction "RST_5") (pintype "passive"))
      (node (ref "C1") (pin "2") (pintype "passive"))
      (node (ref "P3") (pin "4") (pinfunction "4_4") (pintype "passive"))
      (node (ref "R1") (pin "2") (pintype "passive"))
      (node (ref "RST1") (pin "2") (pinfunction "2_2") (pintype "passive"))
      (node (ref "U1") (pin "14") (pinfunction "NRST_14") (pintype "bidirectional"))
    )
    (net (code "92") (name "/VBAT") (class "Default")
      (node (ref "U1") (pin "6") (pinfunction "VBAT_6") (pintype "power_in"))
    )
    (net (code "93") (name "/VCAP1") (class "Default")
      (node (ref "C2") (pin "2") (pintype "passive"))
      (node (ref "U1") (pin "49") (pinfunction "VCAP_1_49") (pintype "power_in"))
    )
    (net (code "94") (name "/VCAP2") (class "Default")
      (node (ref "C3") (pin "2") (pintype "passive"))
      (node (ref "U1") (pin "73") (pinfunction "VCAP_2_73") (pintype "power_in"))
    )
    (net (code "95") (name "3V3") (class "Default")
      (node (ref "2.4'/2.8'LCD") (pin "24") (pinfunction "VDD3.3_24") (pintype "passive"))
      (node (ref "2.4'/2.8'LCD") (pin "25") (pinfunction "VDD3.3_25") (pintype "passive"))
      (node (ref "C13") (pin "2") (pintype "passive"))
      (node (ref "C15") (pin "2") (pintype "passive"))
      (node (ref "C4") (pin "2") (pintype "passive"))
      (node (ref "C5") (pin "2") (pintype "passive"))
      (node (ref "C6") (pin "2") (pintype "passive"))
      (node (ref "C7") (pin "2") (pintype "passive"))
      (node (ref "C8") (pin "1") (pinfunction "1_1") (pintype "passive"))
      (node (ref "CC2") (pin "1") (pinfunction "1_1") (pintype "passive"))
      (node (ref "P1") (pin "5") (pinfunction "5_5") (pintype "passive"))
      (node (ref "P2") (pin "1") (pinfunction "1_1") (pintype "passive"))
      (node (ref "P3") (pin "1") (pinfunction "1_1") (pintype "passive"))
      (node (ref "R1") (pin "1") (pintype "passive"))
      (node (ref "R19") (pin "1") (pintype "passive"))
      (node (ref "R2") (pin "2") (pintype "passive"))
      (node (ref "R20") (pin "1") (pintype "passive"))
      (node (ref "R21") (pin "1") (pintype "passive"))
      (node (ref "R22") (pin "2") (pintype "passive"))
      (node (ref "R23") (pin "2") (pintype "passive"))
      (node (ref "R3") (pin "2") (pintype "passive"))
      (node (ref "R4") (pin "2") (pintype "passive"))
      (node (ref "R5") (pin "2") (pintype "passive"))
      (node (ref "R6") (pin "2") (pintype "passive"))
      (node (ref "U1") (pin "100") (pinfunction "VDD_100") (pintype "power_in"))
      (node (ref "U1") (pin "11") (pinfunction "VDD_11") (pintype "power_in"))
      (node (ref "U1") (pin "19") (pinfunction "VDD_19") (pintype "power_in"))
      (node (ref "U1") (pin "21") (pinfunction "VREF+_21") (pintype "power_in"))
      (node (ref "U1") (pin "22") (pinfunction "VDDA_22") (pintype "power_in"))
      (node (ref "U1") (pin "28") (pinfunction "VDD_28") (pintype "power_in"))
      (node (ref "U1") (pin "50") (pinfunction "VDD_50") (pintype "power_in"))
      (node (ref "U1") (pin "75") (pinfunction "VDD_75") (pintype "power_in"))
      (node (ref "U2") (pin "1") (pintype "passive"))
      (node (ref "U2") (pin "6") (pintype "passive"))
      (node (ref "U3") (pin "4") (pinfunction "3.3V_4") (pintype "passive"))
      (node (ref "U4") (pin "3") (pintype "passive"))
      (node (ref "U4") (pin "6") (pintype "passive"))
      (node (ref "U6") (pin "5") (pinfunction "OUT_5") (pintype "passive"))
      (node (ref "U6") (pin "6") (pinfunction "OUT_6") (pintype "passive"))
      (node (ref "U6") (pin "7") (pinfunction "FB_7") (pintype "passive"))
    )
    (net (code "96") (name "5V") (class "Default")
      (node (ref "2.4'/2.8'LCD") (pin "28") (pinfunction "BL_VDD_28") (pintype "passive"))
      (node (ref "CC1") (pin "1") (pinfunction "1_1") (pintype "passive"))
      (node (ref "CC4") (pin "1") (pinfunction "1_1") (pintype "passive"))
      (node (ref "D3") (pin "K") (pinfunction "K_K") (pintype "passive"))
      (node (ref "R26") (pin "2") (pintype "passive"))
      (node (ref "U6") (pin "3") (pinfunction "IN_3") (pintype "passive"))
      (node (ref "U6") (pin "4") (pinfunction "IN_4") (pintype "passive"))
    )
    (net (code "97") (name "BAT_IN") (class "Default")
      (node (ref "S5") (pin "2") (pinfunction "2_2") (pintype "passive"))
      (node (ref "TP5") (pin "1") (pinfunction "TP_1") (pintype "passive"))
    )
    (net (code "98") (name "GND") (class "Default")
      (node (ref "2.4'/2.8'LCD") (pin "22") (pinfunction "GND_22") (pintype "passive"))
      (node (ref "2.4'/2.8'LCD") (pin "26") (pinfunction "GND_26") (pintype "passive"))
      (node (ref "2.4'/2.8'LCD") (pin "27") (pinfunction "GND_27") (pintype "passive"))
      (node (ref "C1") (pin "1") (pintype "passive"))
      (node (ref "C10") (pin "2") (pintype "passive"))
      (node (ref "C11") (pin "2") (pintype "passive"))
      (node (ref "C12") (pin "2") (pintype "passive"))
      (node (ref "C13") (pin "1") (pintype "passive"))
      (node (ref "C15") (pin "1") (pintype "passive"))
      (node (ref "C18") (pin "1") (pintype "passive"))
      (node (ref "C2") (pin "1") (pintype "passive"))
      (node (ref "C3") (pin "1") (pintype "passive"))
      (node (ref "C4") (pin "1") (pintype "passive"))
      (node (ref "C5") (pin "1") (pintype "passive"))
      (node (ref "C6") (pin "1") (pintype "passive"))
      (node (ref "C7") (pin "1") (pintype "passive"))
      (node (ref "C8") (pin "2") (pinfunction "2_2") (pintype "passive"))
      (node (ref "C9") (pin "2") (pintype "passive"))
      (node (ref "CC1") (pin "2") (pinfunction "2_2") (pintype "passive"))
      (node (ref "CC2") (pin "2") (pinfunction "2_2") (pintype "passive"))
      (node (ref "CC3") (pin "2") (pinfunction "2_2") (pintype "passive"))
      (node (ref "CC4") (pin "2") (pinfunction "2_2") (pintype "passive"))
      (node (ref "K1") (pin "5") (pinfunction "COM_5") (pintype "passive"))
      (node (ref "P1") (pin "1") (pinfunction "1_1") (pintype "passive"))
      (node (ref "P2") (pin "2") (pinfunction "2_2") (pintype "passive"))
      (node (ref "P3") (pin "3") (pinfunction "3_3") (pintype "passive"))
      (node (ref "Q1") (pin "2") (pinfunction "E_2") (pintype "passive"))
      (node (ref "Q2") (pin "2") (pinfunction "E_2") (pintype "passive"))
      (node (ref "R10") (pin "1") (pintype "passive"))
      (node (ref "R27") (pin "1") (pintype "passive"))
      (node (ref "RST1") (pin "1") (pinfunction "1_1") (pintype "passive"))
      (node (ref "S1") (pin "1") (pinfunction "1_1") (pintype "passive"))
      (node (ref "S2") (pin "1") (pinfunction "1_1") (pintype "passive"))
      (node (ref "S3") (pin "1") (pinfunction "1_1") (pintype "passive"))
      (node (ref "S4") (pin "1") (pinfunction "1_1") (pintype "passive"))
      (node (ref "TP6") (pin "1") (pinfunction "TP_1") (pintype "passive"))
      (node (ref "U1") (pin "10") (pinfunction "VSS_10") (pintype "power_in"))
      (node (ref "U1") (pin "20") (pinfunction "VSSA_20") (pintype "power_in"))
      (node (ref "U1") (pin "27") (pinfunction "VSS_27") (pintype "power_in"))
      (node (ref "U1") (pin "74") (pinfunction "VSS_74") (pintype "power_in"))
      (node (ref "U1") (pin "94") (pinfunction "BOOT0/VPP_94") (pintype "input"))
      (node (ref "U1") (pin "99") (pinfunction "VSS_99") (pintype "power_in"))
      (node (ref "U2") (pin "10") (pinfunction "GND_10") (pintype "passive"))
      (node (ref "U2") (pin "3") (pintype "passive"))
      (node (ref "U2") (pin "4") (pintype "passive"))
      (node (ref "U2") (pin "7") (pinfunction "GND_7") (pintype "passive"))
      (node (ref "U2") (pin "8") (pinfunction "GND_8") (pintype "passive"))
      (node (ref "U2") (pin "9") (pinfunction "GND_9") (pintype "passive"))
      (node (ref "U3") (pin "10") (pinfunction "GND_10") (pintype "passive"))
      (node (ref "U3") (pin "11") (pinfunction "GND_11") (pintype "passive"))
      (node (ref "U3") (pin "12") (pinfunction "GND_12") (pintype "passive"))
      (node (ref "U3") (pin "13") (pinfunction "GND_13") (pintype "passive"))
      (node (ref "U3") (pin "6") (pinfunction "GND_6") (pintype "passive"))
      (node (ref "U4") (pin "1") (pintype "passive"))
      (node (ref "U4") (pin "10") (pinfunction "GND_10") (pintype "passive"))
      (node (ref "U4") (pin "4") (pintype "passive"))
      (node (ref "U4") (pin "7") (pinfunction "GND_7") (pintype "passive"))
      (node (ref "U4") (pin "8") (pinfunction "GND_8") (pintype "passive"))
      (node (ref "U4") (pin "9") (pinfunction "GND_9") (pintype "passive"))
      (node (ref "U6") (pin "1") (pinfunction "GND_1") (pintype "passive"))
      (node (ref "U6") (pin "2") (pinfunction "~{EN}_2") (pintype "passive"))
      (node (ref "U7") (pin "2") (pinfunction "SW_EM_2") (pintype "passive"))
      (node (ref "U7") (pin "4") (pinfunction "GND_4") (pintype "power_in"))
      (node (ref "Y2") (pin "3") (pintype "passive"))
    )
    (net (code "99") (name "Net-(LED1-A)") (class "Default")
      (node (ref "LED1") (pin "1") (pinfunction "A_1") (pintype "passive"))
      (node (ref "R19") (pin "2") (pintype "passive"))
    )
    (net (code "100") (name "Net-(LED2-A)") (class "Default")
      (node (ref "LED2") (pin "1") (pinfunction "A_1") (pintype "passive"))
      (node (ref "R20") (pin "2") (pintype "passive"))
    )
    (net (code "101") (name "Net-(LED3-A)") (class "Default")
      (node (ref "LED3") (pin "1") (pinfunction "A_1") (pintype "passive"))
      (node (ref "R21") (pin "2") (pintype "passive"))
    )
    (net (code "102") (name "Net-(Q1-C)") (class "Default")
      (node (ref "D1") (pin "A") (pinfunction "A_A") (pintype "passive"))
      (node (ref "Q1") (pin "3") (pinfunction "C_3") (pintype "passive"))
      (node (ref "TP3") (pin "1") (pinfunction "TP_1") (pintype "passive"))
    )
    (net (code "103") (name "Net-(Q2-C)") (class "Default")
      (node (ref "D2") (pin "A") (pinfunction "A_A") (pintype "passive"))
      (node (ref "Q2") (pin "3") (pinfunction "C_3") (pintype "passive"))
      (node (ref "TP4") (pin "1") (pinfunction "TP_1") (pintype "passive"))
    )
    (net (code "104") (name "Net-(U7-DRV_COLL)") (class "Default")
      (node (ref "R25") (pin "1") (pintype "passive"))
      (node (ref "U7") (pin "8") (pinfunction "DRV_COLL_8") (pintype "open_collector"))
    )
    (net (code "105") (name "Net-(U7-IN-)") (class "Default")
      (node (ref "R26") (pin "1") (pintype "passive"))
      (node (ref "R27") (pin "2") (pintype "passive"))
      (node (ref "U7") (pin "5") (pinfunction "IN-_5") (pintype "input"))
    )
    (net (code "106") (name "Net-(U7-IPK)") (class "Default")
      (node (ref "L2") (pin "1") (pinfunction "1_1") (pintype "passive"))
      (node (ref "R24") (pin "2") (pintype "passive"))
      (node (ref "R25") (pin "2") (pintype "passive"))
      (node (ref "U7") (pin "7") (pinfunction "IPK_7") (pintype "passive"))
    )
    (net (code "107") (name "Net-(U7-SW_COLL)") (class "Default")
      (node (ref "D3") (pin "A") (pinfunction "A_A") (pintype "passive"))
      (node (ref "L2") (pin "2") (pinfunction "2_2") (pintype "passive"))
      (node (ref "U7") (pin "1") (pinfunction "SW_COLL_1") (pintype "passive"))
    )
    (net (code "108") (name "Net-(U7-TIM_CAP)") (class "Default")
      (node (ref "C18") (pin "2") (pintype "passive"))
      (node (ref "U7") (pin "3") (pinfunction "TIM_CAP_3") (pintype "passive"))
    )
    (net (code "109") (name "VCC") (class "Default")
      (node (ref "CC3") (pin "1") (pinfunction "1_1") (pintype "passive"))
      (node (ref "D1") (pin "K") (pinfunction "K_K") (pintype "passive"))
      (node (ref "D2") (pin "K") (pinfunction "K_K") (pintype "passive"))
      (node (ref "R24") (pin "1") (pintype "passive"))
      (node (ref "R9") (pin "2") (pintype "passive"))
      (node (ref "S5") (pin "1") (pinfunction "1_1") (pintype "passive"))
      (node (ref "TP1") (pin "1") (pinfunction "TP_1") (pintype "passive"))
      (node (ref "TP2") (pin "1") (pinfunction "TP_1") (pintype "passive"))
      (node (ref "U7") (pin "6") (pinfunction "VCC_6") (pintype "power_in"))
    )
    (net (code "110") (name "unconnected-(2.4'/2.8'LCD-MO-Pad32)") (class "Default")
      (node (ref "2.4'/2.8'LCD") (pin "32") (pinfunction "MO_32") (pintype "passive"))
    )
    (net (code "111") (name "unconnected-(P3-Pad6)") (class "Default")
      (node (ref "P3") (pin "6") (pinfunction "6_6") (pintype "passive"))
    )
    (net (code "112") (name "unconnected-(S1-Pad3)") (class "Default")
      (node (ref "S1") (pin "3") (pinfunction "3_3") (pintype "passive"))
    )
    (net (code "113") (name "unconnected-(S2-Pad3)") (class "Default")
      (node (ref "S2") (pin "3") (pinfunction "3_3") (pintype "passive"))
    )
    (net (code "114") (name "unconnected-(S3-Pad3)") (class "Default")
      (node (ref "S3") (pin "3") (pinfunction "3_3") (pintype "passive"))
    )
    (net (code "115") (name "unconnected-(S4-Pad3)") (class "Default")
      (node (ref "S4") (pin "3") (pinfunction "3_3") (pintype "passive"))
    )
    (net (code "116") (name "unconnected-(S5-Pad3)") (class "Default")
      (node (ref "S5") (pin "3") (pinfunction "3_3") (pintype "passive"))
    )
    (net (code "117") (name "unconnected-(U3-CD-Pad9)") (class "Default")
      (node (ref "U3") (pin "9") (pinfunction "CD_9") (pintype "passive"))
    )
    (net (code "118") (name "unconnected-(U6-~{RE}-Pad8)") (class "Default")
      (node (ref "U6") (pin "8") (pinfunction "~{RE}_8") (pintype "passive"))
    )
  )
)
